# lipo-charger.net
KiCad netlist of a schematic drawn in Altium Designer
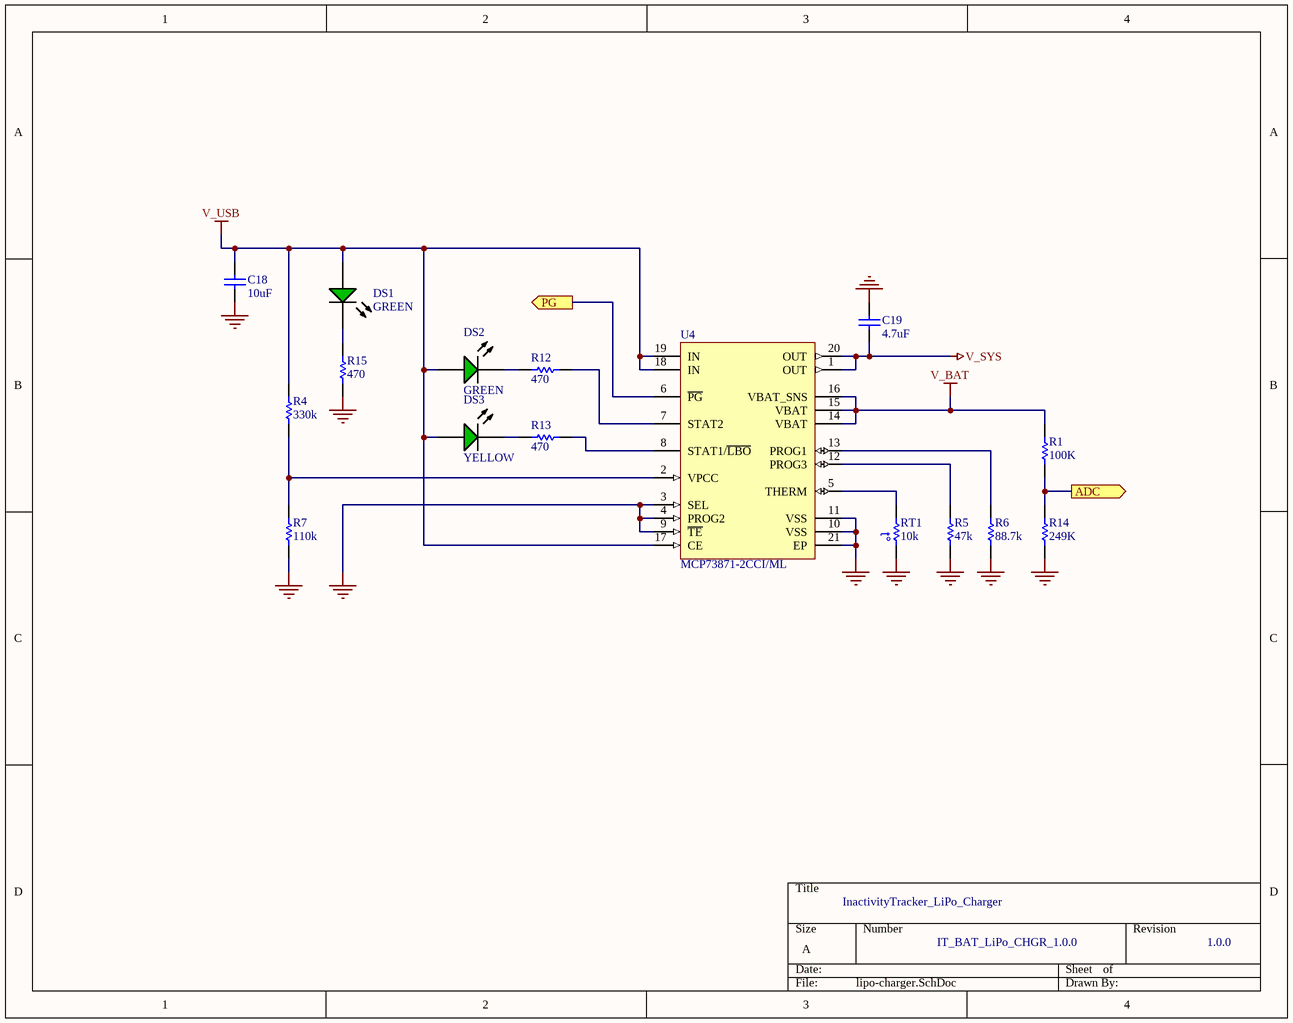
[diagram p0: lipo-charger.SchDoc]

(export (version "E")
  (design (tool "Eeschema 10.0.6"))
  (components
    (comp (ref "C18")
      (value "10uF")
      (footprint "CAPC1005X55X25NL05T10")
      (fields (field (name "PART NUMBER") "GRM155R61A105KE15D") (field (name "MANUFACTURER") "Murata"))
      (libsource (lib "Altium Content Vault") (part "CAP"))
    )
    (comp (ref "C19")
      (value "4.7uF")
      (footprint "CAPC1005X55X25NL05T10")
      (fields (field (name "MANUFACTURER") "Murata") (field (name "PART NUMBER") "GRM155R61C102KA01D"))
      (libsource (lib "Altium Content Vault") (part "CAP"))
    )
    (comp (ref "DS1")
      (value "GREEN")
      (footprint "LITE-ON-LTST-C190GKT-2_V")
      (description "LED Uni-Color Green, 75 mW, 5 V, -30 to 85 degC, 2-Pin SMD, RoHS, Tape and Reel")
      (fields (field (name "MANUFACTURER") "Lite-On"))
      (libsource (lib "Altium Content Vault") (part "LED_GREEN_A1K2-2"))
    )
    (comp (ref "DS2")
      (value "GREEN")
      (footprint "LITE-ON-LTST-C190GKT-2_V")
      (description "LED Uni-Color Green, 75 mW, 5 V, -30 to 85 degC, 2-Pin SMD, RoHS, Tape and Reel")
      (fields (field (name "MANUFACTURER") "Lite-On"))
      (libsource (lib "Altium Content Vault") (part "LED_GREEN_A1K2-2"))
    )
    (comp (ref "DS3")
      (value "YELLOW")
      (footprint "LITE-ON-LTST-C190GKT-2_V")
      (description "LED Uni-Color Green, 75 mW, 5 V, -30 to 85 degC, 2-Pin SMD, RoHS, Tape and Reel")
      (fields (field (name "MANUFACTURER") "Lite-On"))
      (libsource (lib "Altium Content Vault") (part "LED_GREEN_A1K2-2"))
    )
    (comp (ref "R1")
      (value "100K")
      (footprint "RESC1005X40X25ML05T05")
      (description "Chip Resistor, 100 KOhm, +/- 1%, 0.63 W, -55 to 155 degC, 0402 (1005 Metric), RoHS, Tape and Reel")
      (fields (field (name "TOLERANCE") "1%"))
      (libsource (lib "Altium Content Vault") (part "RES-2"))
    )
    (comp (ref "R4")
      (value "330k")
      (footprint "RESC1005X40X25NL05T05")
      (fields (field (name "MANUFACTURER") "Vishay Dale") (field (name "PART NUMBER") "CRCW0402330KFKED"))
      (libsource (lib "Altium Content Vault") (part "RES"))
    )
    (comp (ref "R5")
      (value "47k")
      (footprint "RESC1005X40X25LL05T05")
      (fields (field (name "MANUFACTURER") "Vishay Dale") (field (name "PART NUMBER") "CRCW040247K0JNED"))
      (libsource (lib "Altium Content Vault") (part "RES"))
    )
    (comp (ref "R6")
      (value "88.7k")
      (footprint "RESC1005X40X25NL05T05")
      (fields (field (name "MANUFACTURER") "Vishay Dale") (field (name "PART NUMBER") "CRCW040288K7FKED"))
      (libsource (lib "Altium Content Vault") (part "RES"))
    )
    (comp (ref "R7")
      (value "110k")
      (footprint "RESC1005X40X25NL05T05")
      (fields (field (name "MANUFACTURER") "Vishay Dale") (field (name "PART NUMBER") "CRCW0402110KFKED"))
      (libsource (lib "Altium Content Vault") (part "RES"))
    )
    (comp (ref "R12")
      (value "470")
      (footprint "RESC1005X40X25ML05T05")
      (fields (field (name "PART NUMBER") "CRCW0402470RJNED") (field (name "MANUFACTURER") "Vishay Dale"))
      (libsource (lib "Altium Content Vault") (part "RES"))
    )
    (comp (ref "R13")
      (value "470")
      (footprint "RESC1005X40X25ML05T05")
      (fields (field (name "PART NUMBER") "CRCW0402470RJNED") (field (name "MANUFACTURER") "Vishay Dale"))
      (libsource (lib "Altium Content Vault") (part "RES"))
    )
    (comp (ref "R14")
      (value "249K")
      (footprint "RESC1005X40X25NL05T05")
      (fields (field (name "PART NUMBER") "CRCW0402249KFKED") (field (name "MANUFACTURER") "Vishay Dale"))
      (libsource (lib "Altium Content Vault") (part "RES"))
    )
    (comp (ref "R15")
      (value "470")
      (footprint "RESC1005X40X25ML05T05")
      (fields (field (name "PART NUMBER") "CRCW0402470RJNED") (field (name "MANUFACTURER") "Vishay Dale"))
      (libsource (lib "Altium Content Vault") (part "RES"))
    )
    (comp (ref "RT1")
      (value "10k")
      (footprint "MURA-NCP18XH103F03RB-2_V")
      (description "NTC Thermistor, 10 KOhm, +/- 1%, 0.1 W, -40 to 125 degC, 0603 (1608 Metric), RoHS, Tape and Reel")
      (fields (field (name "MANUFACTURER") "Murata"))
      (libsource (lib "Altium Content Vault") (part "MURA-NCP18XH103F03RB-2"))
    )
    (comp (ref "U4")
      (value "MCP73871-2CCI/ML")
      (footprint "QFN-ML20_M")
      (libsource (lib "Altium Content Vault") (part "PM-BM-MCP73871-SQ21"))
    )
  )
  (nets
    (net (code "1") (name "/ADC") (class "Default")
      (node (ref "R1") (pin "2") (pinfunction "2_2") (pintype "passive"))
      (node (ref "R14") (pin "1") (pinfunction "1_1") (pintype "passive"))
    )
    (net (code "2") (name "/PG") (class "Default")
      (node (ref "U4") (pin "6") (pinfunction "~{PG}_6") (pintype "open_collector"))
    )
    (net (code "3") (name "GND") (class "Default")
      (node (ref "C18") (pin "2") (pinfunction "2_2") (pintype "passive"))
      (node (ref "C19") (pin "2") (pinfunction "2_2") (pintype "passive"))
      (node (ref "R14") (pin "2") (pinfunction "2_2") (pintype "passive"))
      (node (ref "R15") (pin "2") (pinfunction "2_2") (pintype "passive"))
      (node (ref "R5") (pin "2") (pinfunction "2_2") (pintype "passive"))
      (node (ref "R6") (pin "1") (pinfunction "1_1") (pintype "passive"))
      (node (ref "R7") (pin "2") (pinfunction "2_2") (pintype "passive"))
      (node (ref "RT1") (pin "2") (pinfunction "2_2") (pintype "passive"))
      (node (ref "U4") (pin "10") (pinfunction "VSS_10") (pintype "power_in"))
      (node (ref "U4") (pin "11") (pinfunction "VSS_11") (pintype "power_in"))
      (node (ref "U4") (pin "21") (pinfunction "EP_21") (pintype "power_in"))
      (node (ref "U4") (pin "3") (pinfunction "SEL_3") (pintype "input"))
      (node (ref "U4") (pin "4") (pinfunction "PROG2_4") (pintype "input"))
      (node (ref "U4") (pin "9") (pinfunction "~{TE}_9") (pintype "input"))
    )
    (net (code "4") (name "Net-(DS1-K)") (class "Default")
      (node (ref "DS1") (pin "2") (pinfunction "K_2") (pintype "passive"))
      (node (ref "R15") (pin "1") (pinfunction "1_1") (pintype "passive"))
    )
    (net (code "5") (name "Net-(DS2-K)") (class "Default")
      (node (ref "DS2") (pin "2") (pinfunction "K_2") (pintype "passive"))
      (node (ref "R12") (pin "1") (pinfunction "1_1") (pintype "passive"))
    )
    (net (code "6") (name "Net-(DS3-K)") (class "Default")
      (node (ref "DS3") (pin "2") (pinfunction "K_2") (pintype "passive"))
      (node (ref "R13") (pin "1") (pinfunction "1_1") (pintype "passive"))
    )
    (net (code "7") (name "Net-(U4-PROG1)") (class "Default")
      (node (ref "R6") (pin "2") (pinfunction "2_2") (pintype "passive"))
      (node (ref "U4") (pin "13") (pinfunction "PROG1_13") (pintype "bidirectional"))
    )
    (net (code "8") (name "Net-(U4-PROG3)") (class "Default")
      (node (ref "R5") (pin "1") (pinfunction "1_1") (pintype "passive"))
      (node (ref "U4") (pin "12") (pinfunction "PROG3_12") (pintype "bidirectional"))
    )
    (net (code "9") (name "Net-(U4-STAT1{slash}~{LBO})") (class "Default")
      (node (ref "R13") (pin "2") (pinfunction "2_2") (pintype "passive"))
      (node (ref "U4") (pin "8") (pinfunction "STAT1/~{LBO}_8") (pintype "open_collector"))
    )
    (net (code "10") (name "Net-(U4-STAT2)") (class "Default")
      (node (ref "R12") (pin "2") (pinfunction "2_2") (pintype "passive"))
      (node (ref "U4") (pin "7") (pinfunction "STAT2_7") (pintype "open_collector"))
    )
    (net (code "11") (name "Net-(U4-THERM)") (class "Default")
      (node (ref "RT1") (pin "1") (pinfunction "1_1") (pintype "passive"))
      (node (ref "U4") (pin "5") (pinfunction "THERM_5") (pintype "bidirectional"))
    )
    (net (code "12") (name "Net-(U4-VPCC)") (class "Default")
      (node (ref "R4") (pin "2") (pinfunction "2_2") (pintype "passive"))
      (node (ref "R7") (pin "1") (pinfunction "1_1") (pintype "passive"))
      (node (ref "U4") (pin "2") (pinfunction "VPCC_2") (pintype "input"))
    )
    (net (code "13") (name "V_BAT") (class "Default")
      (node (ref "R1") (pin "1") (pinfunction "1_1") (pintype "passive"))
      (node (ref "U4") (pin "14") (pinfunction "VBAT_14") (pintype "power_in"))
      (node (ref "U4") (pin "15") (pinfunction "VBAT_15") (pintype "power_in"))
      (node (ref "U4") (pin "16") (pinfunction "VBAT_SNS_16") (pintype "power_in"))
    )
    (net (code "14") (name "V_SYS") (class "Default")
      (node (ref "C19") (pin "1") (pinfunction "1_1") (pintype "passive"))
      (node (ref "U4") (pin "1") (pinfunction "OUT_1") (pintype "output"))
      (node (ref "U4") (pin "20") (pinfunction "OUT_20") (pintype "output"))
    )
    (net (code "15") (name "V_USB") (class "Default")
      (node (ref "C18") (pin "1") (pinfunction "1_1") (pintype "passive"))
      (node (ref "DS1") (pin "1") (pinfunction "A_1") (pintype "passive"))
      (node (ref "DS2") (pin "1") (pinfunction "A_1") (pintype "passive"))
      (node (ref "DS3") (pin "1") (pinfunction "A_1") (pintype "passive"))
      (node (ref "R4") (pin "1") (pinfunction "1_1") (pintype "passive"))
      (node (ref "U4") (pin "17") (pinfunction "CE_17") (pintype "input"))
      (node (ref "U4") (pin "18") (pinfunction "IN_18") (pintype "power_in"))
      (node (ref "U4") (pin "19") (pinfunction "IN_19") (pintype "power_in"))
    )
  )
)
